# design.net
KiCad netlist of a schematic drawn in EasyEDA Pro
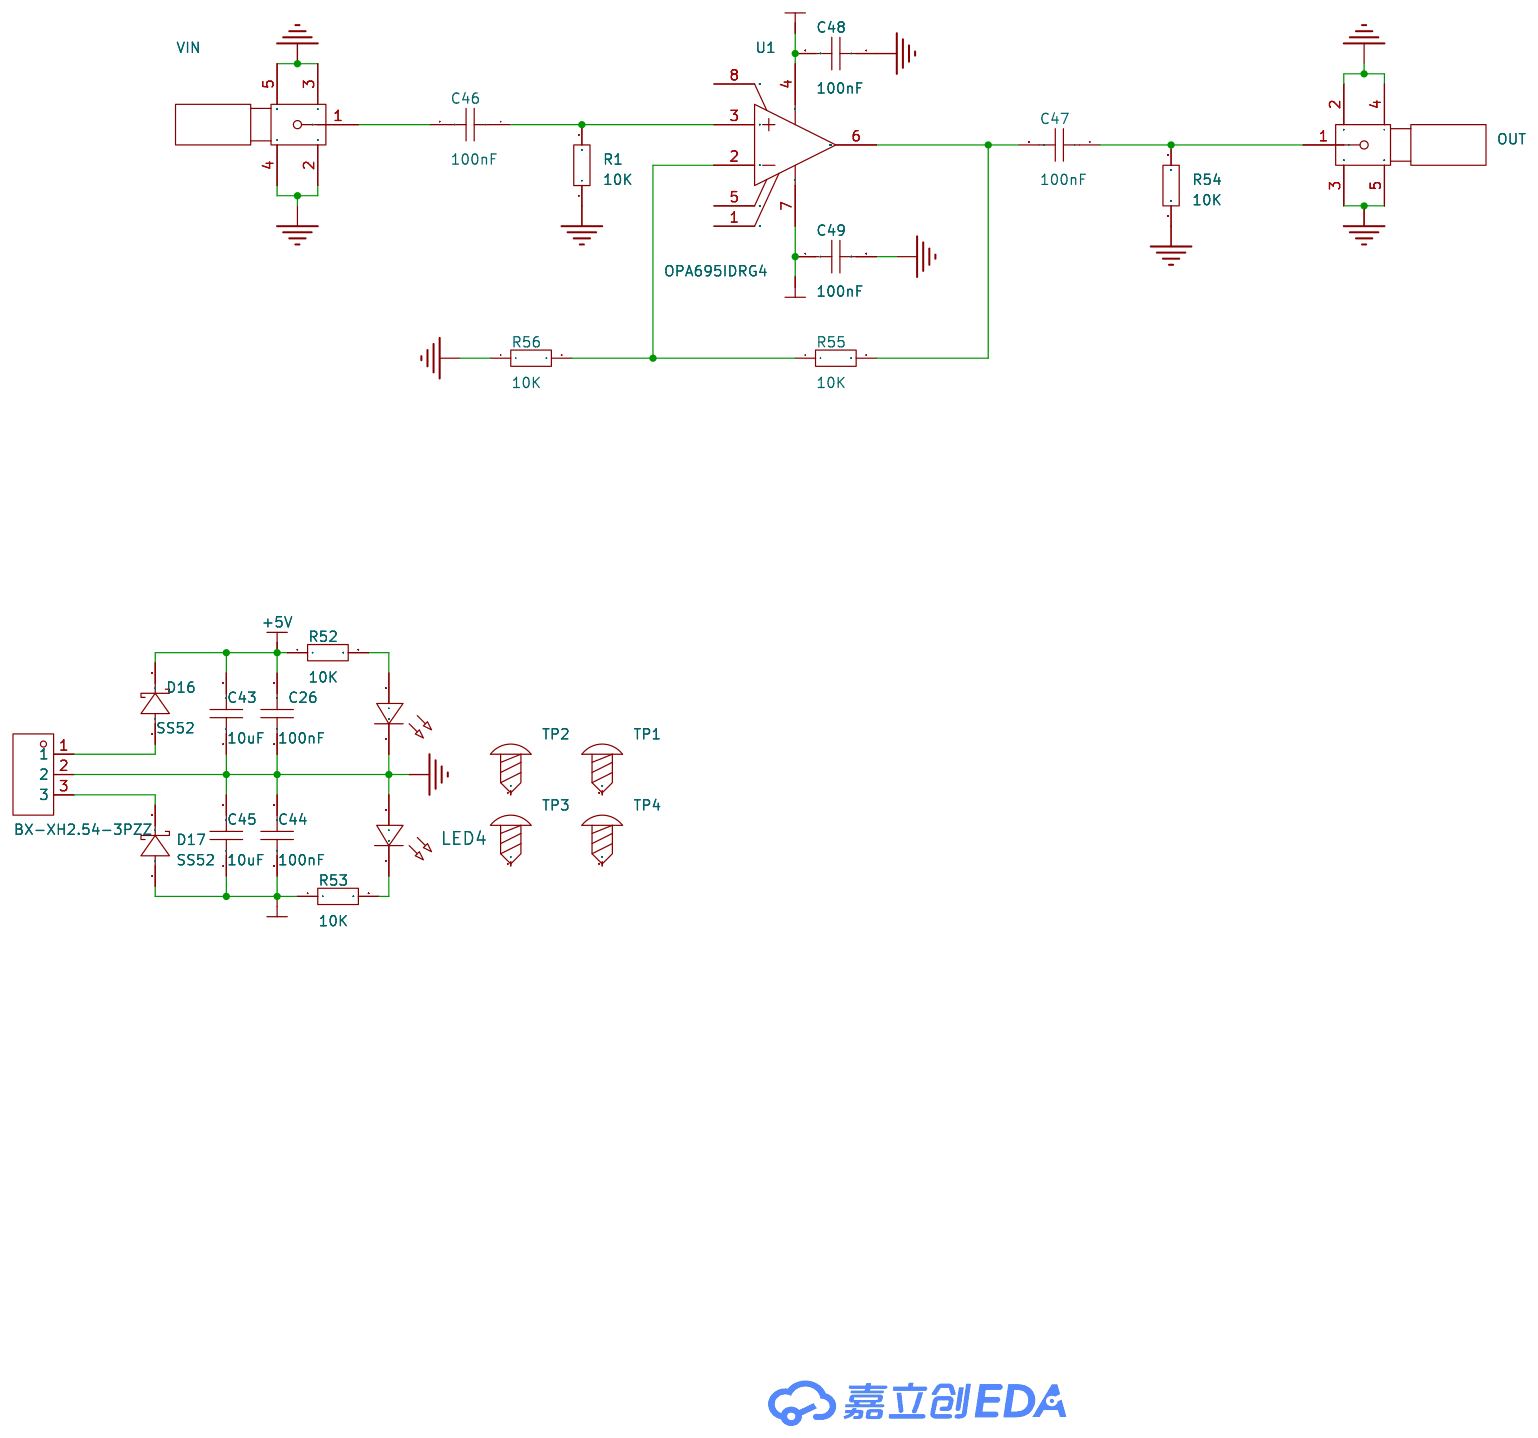
[diagram p0: schematic sheet]

(export (version "E")
  (design (tool "Eeschema 10.0.6"))
  (components
    (comp (ref "C26")
      (value "100nF")
      (footprint "easyedapro:C0603")
      (libsource (lib "easyedapro") (part "CapAcitance"))
    )
    (comp (ref "C43")
      (value "10uF")
      (footprint "easyedapro:C0603")
      (libsource (lib "easyedapro") (part "CapAcitance"))
    )
    (comp (ref "C44")
      (value "100nF")
      (footprint "easyedapro:C0603")
      (libsource (lib "easyedapro") (part "CapAcitance"))
    )
    (comp (ref "C45")
      (value "10uF")
      (footprint "easyedapro:C0603")
      (libsource (lib "easyedapro") (part "CapAcitance"))
    )
    (comp (ref "C46")
      (value "100nF")
      (footprint "easyedapro:C0603")
      (libsource (lib "easyedapro") (part "CapAcitance"))
    )
    (comp (ref "C47")
      (value "100nF")
      (footprint "easyedapro:C0603")
      (libsource (lib "easyedapro") (part "CapAcitance"))
    )
    (comp (ref "C48")
      (value "100nF")
      (footprint "easyedapro:C0603")
      (libsource (lib "easyedapro") (part "CapAcitance"))
    )
    (comp (ref "C49")
      (value "100nF")
      (footprint "easyedapro:C0603")
      (libsource (lib "easyedapro") (part "CapAcitance"))
    )
    (comp (ref "D16")
      (value "SS52")
      (footprint "easyedapro:SMA_L4.3-W2.6-LS5.1-R-RD")
      (description "二极管配置:独立式;正向压降(Vf):550mV@5A;直流反向耐压(Vr):20V;平均整流电流(Io):5A;")
      (fields (field (name "Manufacturer") "TWGMC(台湾迪嘉)"))
      (libsource (lib "easyedapro") (part "SS52_C727064"))
    )
    (comp (ref "D17")
      (value "SS52")
      (footprint "easyedapro:SMA_L4.3-W2.6-LS5.1-R-RD")
      (description "二极管配置:独立式;正向压降(Vf):550mV@5A;直流反向耐压(Vr):20V;平均整流电流(Io):5A;")
      (fields (field (name "Manufacturer") "TWGMC(台湾迪嘉)"))
      (libsource (lib "easyedapro") (part "SS52_C727064"))
    )
    (comp (ref "LED3")
      (value "~")
      (footprint "easyedapro:LED_0603")
      (libsource (lib "easyedapro") (part "LED_R"))
    )
    (comp (ref "LED4")
      (value "~")
      (footprint "easyedapro:LED_0603")
      (libsource (lib "easyedapro") (part "LED_R"))
    )
    (comp (ref "OUT")
      (value "被测信号")
      (footprint "easyedapro:SMA-SMD_SMA-KE")
      (libsource (lib "easyedapro") (part "SMA-KE"))
    )
    (comp (ref "R1") (value "10K") (footprint "easyedapro:R0603") (libsource (lib "easyedapro") (part "电阻")))
    (comp (ref "R52") (value "10K") (footprint "easyedapro:R0603") (libsource (lib "easyedapro") (part "电阻")))
    (comp (ref "R53") (value "10K") (footprint "easyedapro:R0603") (libsource (lib "easyedapro") (part "电阻")))
    (comp (ref "R54") (value "10K") (footprint "easyedapro:R0603") (libsource (lib "easyedapro") (part "电阻")))
    (comp (ref "R55") (value "10K") (footprint "easyedapro:R0603") (libsource (lib "easyedapro") (part "电阻")))
    (comp (ref "R56") (value "10K") (footprint "easyedapro:R0603") (libsource (lib "easyedapro") (part "电阻")))
    (comp (ref "TP1") (value "~") (footprint "easyedapro:M2螺丝") (libsource (lib "easyedapro") (part "螺丝孔")))
    (comp (ref "TP2") (value "~") (footprint "easyedapro:M2螺丝") (libsource (lib "easyedapro") (part "螺丝孔")))
    (comp (ref "TP3") (value "~") (footprint "easyedapro:M2螺丝") (libsource (lib "easyedapro") (part "螺丝孔")))
    (comp (ref "TP4") (value "~") (footprint "easyedapro:M2螺丝") (libsource (lib "easyedapro") (part "螺丝孔")))
    (comp (ref "U1")
      (value "OPA695IDRG4")
      (footprint "easyedapro:SOIC-8_L5.0-W4.0-P1.27-LS6.1-BL")
      (description "OPA695 具有禁用功能的超宽带电流反馈运算放大器")
      (fields (field (name "Manufacturer") "TI(德州仪器)"))
      (libsource (lib "easyedapro") (part "OPA695IDRG4"))
    )
    (comp (ref "U2")
      (value "BX-XH2.54-3PZZ")
      (footprint "easyedapro:CONN-TH_3P-P2.50_BX-XH2.54-3PZZ")
      (fields (field (name "Manufacturer") "Bossie(博锡)"))
      (libsource (lib "easyedapro") (part "BX-XH2.54-3PZZ"))
    )
    (comp (ref "VIN")
      (value "被测信号")
      (footprint "easyedapro:SMA-SMD_SMA-KE")
      (libsource (lib "easyedapro") (part "SMA-KE"))
    )
  )
  (nets
    (net (code "1") (name "+5V") (class "Default")
      (node (ref "C26") (pin "2") (pinfunction "2_2") (pintype "input"))
      (node (ref "C43") (pin "2") (pinfunction "2_2") (pintype "input"))
      (node (ref "C49") (pin "1") (pinfunction "1_1") (pintype "input"))
      (node (ref "D16") (pin "2") (pinfunction "K_2") (pintype "unspecified"))
      (node (ref "R52") (pin "1") (pinfunction "1_1") (pintype "input"))
      (node (ref "U1") (pin "7") (pinfunction "+VS_7") (pintype "unspecified"))
    )
    (net (code "2") (name "-5V") (class "Default")
      (node (ref "C44") (pin "1") (pinfunction "1_1") (pintype "input"))
      (node (ref "C45") (pin "1") (pinfunction "1_1") (pintype "input"))
      (node (ref "C48") (pin "2") (pinfunction "2_2") (pintype "input"))
      (node (ref "D17") (pin "1") (pinfunction "A_1") (pintype "unspecified"))
      (node (ref "R53") (pin "1") (pinfunction "1_1") (pintype "input"))
      (node (ref "U1") (pin "4") (pinfunction "-VS_4") (pintype "unspecified"))
    )
    (net (code "3") (name "GND") (class "Default")
      (node (ref "C26") (pin "1") (pinfunction "1_1") (pintype "input"))
      (node (ref "C43") (pin "1") (pinfunction "1_1") (pintype "input"))
      (node (ref "C44") (pin "2") (pinfunction "2_2") (pintype "input"))
      (node (ref "C45") (pin "2") (pinfunction "2_2") (pintype "input"))
      (node (ref "C48") (pin "1") (pinfunction "1_1") (pintype "input"))
      (node (ref "C49") (pin "2") (pinfunction "2_2") (pintype "input"))
      (node (ref "LED3") (pin "1") (pinfunction "C_1") (pintype "input"))
      (node (ref "LED4") (pin "2") (pinfunction "A_2") (pintype "input"))
      (node (ref "OUT") (pin "2") (pinfunction "2_2") (pintype "input"))
      (node (ref "OUT") (pin "3") (pinfunction "3_3") (pintype "input"))
      (node (ref "OUT") (pin "4") (pinfunction "4_4") (pintype "input"))
      (node (ref "OUT") (pin "5") (pinfunction "5_5") (pintype "input"))
      (node (ref "R1") (pin "1") (pinfunction "1_1") (pintype "input"))
      (node (ref "R54") (pin "1") (pinfunction "1_1") (pintype "input"))
      (node (ref "R56") (pin "1") (pinfunction "1_1") (pintype "input"))
      (node (ref "U2") (pin "2") (pinfunction "2_2") (pintype "unspecified"))
      (node (ref "VIN") (pin "2") (pinfunction "2_2") (pintype "input"))
      (node (ref "VIN") (pin "3") (pinfunction "3_3") (pintype "input"))
      (node (ref "VIN") (pin "4") (pinfunction "4_4") (pintype "input"))
      (node (ref "VIN") (pin "5") (pinfunction "5_5") (pintype "input"))
    )
    (net (code "4") (name "Net-(C46-Pad2)") (class "Default")
      (node (ref "C46") (pin "2") (pinfunction "2_2") (pintype "input"))
      (node (ref "VIN") (pin "1") (pinfunction "1_1") (pintype "input"))
    )
    (net (code "5") (name "Net-(C47-Pad1)") (class "Default")
      (node (ref "C47") (pin "1") (pinfunction "1_1") (pintype "input"))
      (node (ref "OUT") (pin "1") (pinfunction "1_1") (pintype "input"))
      (node (ref "R54") (pin "2") (pinfunction "2_2") (pintype "input"))
    )
    (net (code "6") (name "Net-(D16-A)") (class "Default")
      (node (ref "D16") (pin "1") (pinfunction "A_1") (pintype "unspecified"))
      (node (ref "U2") (pin "1") (pinfunction "1_1") (pintype "unspecified"))
    )
    (net (code "7") (name "Net-(D17-K)") (class "Default")
      (node (ref "D17") (pin "2") (pinfunction "K_2") (pintype "unspecified"))
      (node (ref "U2") (pin "3") (pinfunction "3_3") (pintype "unspecified"))
    )
    (net (code "8") (name "Net-(LED3-A)") (class "Default")
      (node (ref "LED3") (pin "2") (pinfunction "A_2") (pintype "input"))
      (node (ref "R52") (pin "2") (pinfunction "2_2") (pintype "input"))
    )
    (net (code "9") (name "Net-(LED4-C)") (class "Default")
      (node (ref "LED4") (pin "1") (pinfunction "C_1") (pintype "input"))
      (node (ref "R53") (pin "2") (pinfunction "2_2") (pintype "input"))
    )
    (net (code "10") (name "Net-(U1-+IN)") (class "Default")
      (node (ref "C46") (pin "1") (pinfunction "1_1") (pintype "input"))
      (node (ref "R1") (pin "2") (pinfunction "2_2") (pintype "input"))
      (node (ref "U1") (pin "3") (pinfunction "+IN_3") (pintype "unspecified"))
    )
    (net (code "11") (name "Net-(U1--IN)") (class "Default")
      (node (ref "R55") (pin "1") (pinfunction "1_1") (pintype "input"))
      (node (ref "R56") (pin "2") (pinfunction "2_2") (pintype "input"))
      (node (ref "U1") (pin "2") (pinfunction "-IN_2") (pintype "unspecified"))
    )
    (net (code "12") (name "Net-(U1-Output)") (class "Default")
      (node (ref "C47") (pin "2") (pinfunction "2_2") (pintype "input"))
      (node (ref "R55") (pin "2") (pinfunction "2_2") (pintype "input"))
      (node (ref "U1") (pin "6") (pinfunction "Output_6") (pintype "output"))
    )
    (net (code "13") (name "unconnected-(TP1-Pad1)") (class "Default")
      (node (ref "TP1") (pin "1") (pinfunction "1_1") (pintype "input"))
    )
    (net (code "14") (name "unconnected-(TP2-Pad1)") (class "Default")
      (node (ref "TP2") (pin "1") (pinfunction "1_1") (pintype "input"))
    )
    (net (code "15") (name "unconnected-(TP3-Pad1)") (class "Default")
      (node (ref "TP3") (pin "1") (pinfunction "1_1") (pintype "input"))
    )
    (net (code "16") (name "unconnected-(TP4-Pad1)") (class "Default")
      (node (ref "TP4") (pin "1") (pinfunction "1_1") (pintype "input"))
    )
    (net (code "17") (name "unconnected-(U1-DIS#-Pad8)") (class "Default")
      (node (ref "U1") (pin "8") (pinfunction "DIS#_8") (pintype "unspecified"))
    )
    (net (code "18") (name "unconnected-(U1-NC-Pad1)") (class "Default")
      (node (ref "U1") (pin "1") (pinfunction "NC_1") (pintype "unspecified"))
    )
    (net (code "19") (name "unconnected-(U1-NC-Pad5)") (class "Default")
      (node (ref "U1") (pin "5") (pinfunction "NC_5") (pintype "unspecified"))
    )
  )
)
